# switch.net
KiCad netlist of a schematic drawn in EAGLE
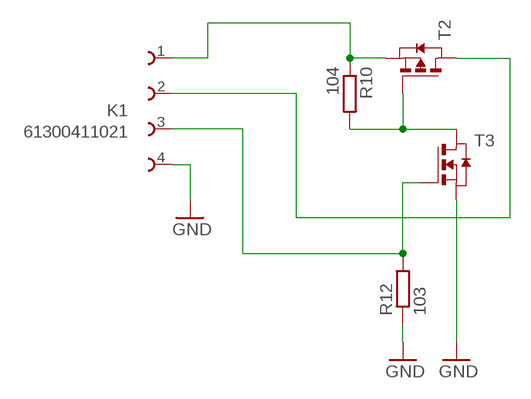
[diagram p0: schematic, sheet 1]

(export (version "E")
  (design (tool "Eeschema 10.0.6"))
  (components
    (comp (ref "K1")
      (value "61300411021")
      (footprint "eagle-import:61300411021")
      (libsource (lib "eagle-import") (part "61300411021"))
    )
    (comp (ref "R10")
      (value "104")
      (footprint "eagle-import:R0603")
      (libsource (lib "eagle-import") (part "R-EU_R0603"))
    )
    (comp (ref "R12")
      (value "103")
      (footprint "eagle-import:R0603")
      (libsource (lib "eagle-import") (part "R-EU_R0603"))
    )
    (comp (ref "T2")
      (value "PMOSSOT23")
      (footprint "eagle-import:SOT-23")
      (libsource (lib "eagle-import") (part "PMOSSOT23"))
    )
    (comp (ref "T3")
      (value "NMOSSOT23")
      (footprint "eagle-import:SOT-23")
      (libsource (lib "eagle-import") (part "NMOSSOT23"))
    )
  )
  (nets
    (net (code "1") (name "GND") (class "Default")
      (node (ref "K1") (pin "4") (pinfunction "4_4") (pintype "passive"))
      (node (ref "R12") (pin "1") (pinfunction "1_1") (pintype "passive"))
      (node (ref "T3") (pin "2") (pinfunction "S_2") (pintype "passive"))
    )
    (net (code "2") (name "Net-(T2-D)") (class "Default")
      (node (ref "K1") (pin "2") (pinfunction "2_2") (pintype "passive"))
      (node (ref "T2") (pin "1") (pinfunction "D_1") (pintype "passive"))
    )
    (net (code "3") (name "Net-(T2-G)") (class "Default")
      (node (ref "R10") (pin "2") (pinfunction "2_2") (pintype "passive"))
      (node (ref "T2") (pin "3") (pinfunction "G_3") (pintype "passive"))
      (node (ref "T3") (pin "1") (pinfunction "D_1") (pintype "passive"))
    )
    (net (code "4") (name "Net-(T2-S)") (class "Default")
      (node (ref "K1") (pin "1") (pinfunction "1_1") (pintype "passive"))
      (node (ref "R10") (pin "1") (pinfunction "1_1") (pintype "passive"))
      (node (ref "T2") (pin "2") (pinfunction "S_2") (pintype "passive"))
    )
    (net (code "5") (name "Net-(T3-G)") (class "Default")
      (node (ref "K1") (pin "3") (pinfunction "3_3") (pintype "passive"))
      (node (ref "R12") (pin "2") (pinfunction "2_2") (pintype "passive"))
      (node (ref "T3") (pin "3") (pinfunction "G_3") (pintype "passive"))
    )
  )
)
